# SI4689_Fm_Module.net
KiCad netlist of a schematic drawn in EAGLE
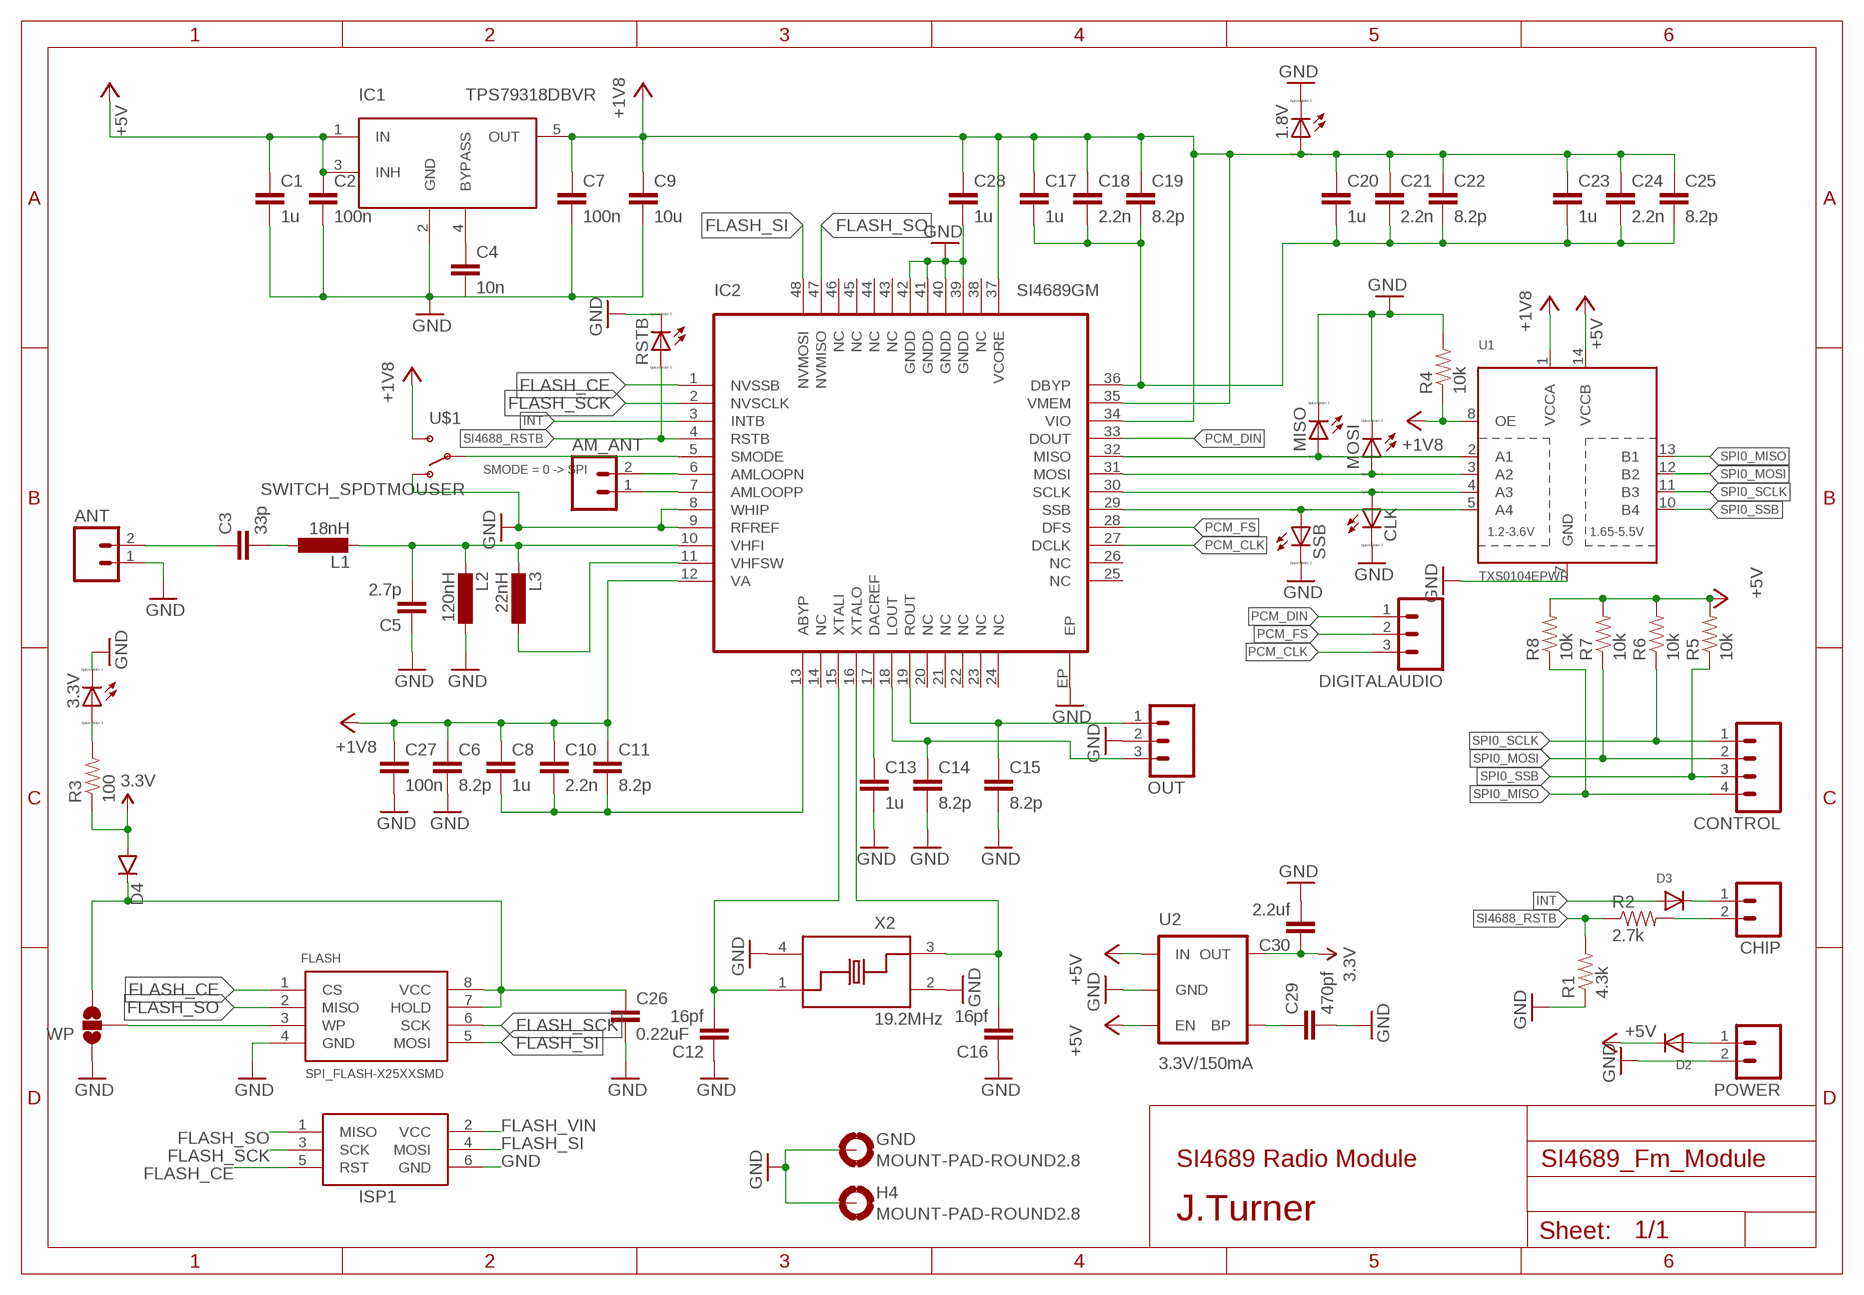
[diagram p0: schematic, sheet 1]

(export (version "E")
  (design (tool "Eeschema 10.0.6"))
  (components
    (comp (ref "1.8V")
      (value "LED_ESML0603")
      (footprint "eagle-import:LED_SML0603")
      (libsource (lib "eagle-import") (part "LED_ESML0603"))
    )
    (comp (ref "3.3V")
      (value "LED_ESML0603")
      (footprint "eagle-import:LED_SML0603")
      (libsource (lib "eagle-import") (part "LED_ESML0603"))
    )
    (comp (ref "AM_ANT")
      (value "M02")
      (footprint "eagle-import:02P")
      (libsource (lib "eagle-import") (part "M02"))
    )
    (comp (ref "ANT")
      (value "M02")
      (footprint "eagle-import:02P")
      (libsource (lib "eagle-import") (part "M02"))
    )
    (comp (ref "C1")
      (value "1u")
      (footprint "eagle-import:SMD0603")
      (libsource (lib "eagle-import") (part "C0603"))
    )
    (comp (ref "C2")
      (value "100n")
      (footprint "eagle-import:SMD0603")
      (libsource (lib "eagle-import") (part "C0603"))
    )
    (comp (ref "C3")
      (value "33p")
      (footprint "eagle-import:0603-CAP")
      (libsource (lib "eagle-import") (part "0603CAP"))
    )
    (comp (ref "C4")
      (value "10n")
      (footprint "eagle-import:SMD0603")
      (libsource (lib "eagle-import") (part "C0603"))
    )
    (comp (ref "C5")
      (value "2.7p")
      (footprint "eagle-import:0603-CAP")
      (libsource (lib "eagle-import") (part "0603CAP"))
    )
    (comp (ref "C6")
      (value "8.2p")
      (footprint "eagle-import:SMD0603")
      (libsource (lib "eagle-import") (part "C0603"))
    )
    (comp (ref "C7")
      (value "100n")
      (footprint "eagle-import:SMD0603")
      (libsource (lib "eagle-import") (part "C0603"))
    )
    (comp (ref "C8")
      (value "1u")
      (footprint "eagle-import:SMD0603")
      (libsource (lib "eagle-import") (part "C0603"))
    )
    (comp (ref "C9")
      (value "10u")
      (footprint "eagle-import:SMD0603")
      (libsource (lib "eagle-import") (part "C0603"))
    )
    (comp (ref "C10")
      (value "2.2n")
      (footprint "eagle-import:SMD0603")
      (libsource (lib "eagle-import") (part "C0603"))
    )
    (comp (ref "C11")
      (value "8.2p")
      (footprint "eagle-import:SMD0603")
      (libsource (lib "eagle-import") (part "C0603"))
    )
    (comp (ref "C12")
      (value "16pf")
      (footprint "eagle-import:0603-CAP")
      (libsource (lib "eagle-import") (part "0603CAP"))
    )
    (comp (ref "C13")
      (value "1u")
      (footprint "eagle-import:SMD0603")
      (libsource (lib "eagle-import") (part "C0603"))
    )
    (comp (ref "C14")
      (value "8.2p")
      (footprint "eagle-import:SMD0603")
      (libsource (lib "eagle-import") (part "C0603"))
    )
    (comp (ref "C15")
      (value "8.2p")
      (footprint "eagle-import:SMD0603")
      (libsource (lib "eagle-import") (part "C0603"))
    )
    (comp (ref "C16")
      (value "16pf")
      (footprint "eagle-import:0603-CAP")
      (libsource (lib "eagle-import") (part "0603CAP"))
    )
    (comp (ref "C17")
      (value "1u")
      (footprint "eagle-import:SMD0603")
      (libsource (lib "eagle-import") (part "C0603"))
    )
    (comp (ref "C18")
      (value "2.2n")
      (footprint "eagle-import:SMD0603")
      (libsource (lib "eagle-import") (part "C0603"))
    )
    (comp (ref "C19")
      (value "8.2p")
      (footprint "eagle-import:SMD0603")
      (libsource (lib "eagle-import") (part "C0603"))
    )
    (comp (ref "C20")
      (value "1u")
      (footprint "eagle-import:SMD0603")
      (libsource (lib "eagle-import") (part "C0603"))
    )
    (comp (ref "C21")
      (value "2.2n")
      (footprint "eagle-import:SMD0603")
      (libsource (lib "eagle-import") (part "C0603"))
    )
    (comp (ref "C22")
      (value "8.2p")
      (footprint "eagle-import:SMD0603")
      (libsource (lib "eagle-import") (part "C0603"))
    )
    (comp (ref "C23")
      (value "1u")
      (footprint "eagle-import:SMD0603")
      (libsource (lib "eagle-import") (part "C0603"))
    )
    (comp (ref "C24")
      (value "2.2n")
      (footprint "eagle-import:SMD0603")
      (libsource (lib "eagle-import") (part "C0603"))
    )
    (comp (ref "C25")
      (value "8.2p")
      (footprint "eagle-import:SMD0603")
      (libsource (lib "eagle-import") (part "C0603"))
    )
    (comp (ref "C26")
      (value "0.22uF")
      (footprint "eagle-import:0603-CAP")
      (libsource (lib "eagle-import") (part "0603CAP"))
    )
    (comp (ref "C27")
      (value "100n")
      (footprint "eagle-import:SMD0603")
      (libsource (lib "eagle-import") (part "C0603"))
    )
    (comp (ref "C28")
      (value "1u")
      (footprint "eagle-import:SMD0603")
      (libsource (lib "eagle-import") (part "C0603"))
    )
    (comp (ref "C29")
      (value "470pf")
      (footprint "eagle-import:0603-CAP")
      (libsource (lib "eagle-import") (part "0603CAP"))
    )
    (comp (ref "C30")
      (value "2.2uf")
      (footprint "eagle-import:0603-CAP")
      (libsource (lib "eagle-import") (part "0603CAP"))
    )
    (comp (ref "CHIP")
      (value "M02")
      (footprint "eagle-import:02P")
      (libsource (lib "eagle-import") (part "M02"))
    )
    (comp (ref "CLK")
      (value "LED_ESML0603")
      (footprint "eagle-import:LED_SML0603")
      (libsource (lib "eagle-import") (part "LED_ESML0603"))
    )
    (comp (ref "CONTROL")
      (value "M04")
      (footprint "eagle-import:04P")
      (libsource (lib "eagle-import") (part "M04"))
    )
    (comp (ref "D2")
      (value "DIODESOD-323F")
      (footprint "eagle-import:SOD-323F")
      (libsource (lib "eagle-import") (part "DIODESOD-323F"))
    )
    (comp (ref "D3")
      (value "DIODESOD-323F")
      (footprint "eagle-import:SOD-323F")
      (libsource (lib "eagle-import") (part "DIODESOD-323F"))
    )
    (comp (ref "D4")
      (value "DIODESOD523")
      (footprint "eagle-import:SOD523")
      (libsource (lib "eagle-import") (part "DIODESOD523"))
    )
    (comp (ref "DIGITALAUDIO")
      (value "M03")
      (footprint "eagle-import:03P")
      (libsource (lib "eagle-import") (part "M03"))
    )
    (comp (ref "FLASH")
      (value "SPI_FLASH-X25XXSMD")
      (footprint "eagle-import:SO08")
      (libsource (lib "eagle-import") (part "SPI_FLASH-X25XXSMD"))
    )
    (comp (ref "GND")
      (value "MOUNT-PAD-ROUND2.8")
      (footprint "eagle-import:2,8-PAD")
      (libsource (lib "eagle-import") (part "MOUNT-PAD-ROUND2.8"))
    )
    (comp (ref "H4")
      (value "MOUNT-PAD-ROUND2.8")
      (footprint "eagle-import:2,8-PAD")
      (libsource (lib "eagle-import") (part "MOUNT-PAD-ROUND2.8"))
    )
    (comp (ref "IC1")
      (value "TPS79318DBVR")
      (footprint "eagle-import:SOT23-5")
      (libsource (lib "eagle-import") (part "TPS79318DBVR"))
    )
    (comp (ref "IC2")
      (value "SI4689GM")
      (footprint "eagle-import:QFN48")
      (libsource (lib "eagle-import") (part "SI4689GM"))
    )
    (comp (ref "ISP1")
      (value "AVRISP-6")
      (footprint "eagle-import:AVRISP")
      (libsource (lib "eagle-import") (part "AVRISP-6"))
    )
    (comp (ref "L1")
      (value "18nH")
      (footprint "eagle-import:SMD0402")
      (libsource (lib "eagle-import") (part "L0402"))
    )
    (comp (ref "L2")
      (value "120nH")
      (footprint "eagle-import:SMD0402")
      (libsource (lib "eagle-import") (part "L0402"))
    )
    (comp (ref "L3")
      (value "22nH")
      (footprint "eagle-import:SMD0402")
      (libsource (lib "eagle-import") (part "L0402"))
    )
    (comp (ref "MISO")
      (value "LED_ESML0603")
      (footprint "eagle-import:LED_SML0603")
      (libsource (lib "eagle-import") (part "LED_ESML0603"))
    )
    (comp (ref "MOSI")
      (value "LED_ESML0603")
      (footprint "eagle-import:LED_SML0603")
      (libsource (lib "eagle-import") (part "LED_ESML0603"))
    )
    (comp (ref "OUT")
      (value "M03")
      (footprint "eagle-import:03P")
      (libsource (lib "eagle-import") (part "M03"))
    )
    (comp (ref "POWER")
      (value "M02")
      (footprint "eagle-import:02P")
      (libsource (lib "eagle-import") (part "M02"))
    )
    (comp (ref "R1")
      (value "4.3k")
      (footprint "eagle-import:0603-RES")
      (libsource (lib "eagle-import") (part "RESISTOR0603"))
    )
    (comp (ref "R2")
      (value "2.7k")
      (footprint "eagle-import:0603-RES")
      (libsource (lib "eagle-import") (part "RESISTOR0603"))
    )
    (comp (ref "R3")
      (value "100")
      (footprint "eagle-import:0603-RES")
      (libsource (lib "eagle-import") (part "RESISTOR0603"))
    )
    (comp (ref "R4")
      (value "10k")
      (footprint "eagle-import:0603-RES")
      (libsource (lib "eagle-import") (part "RESISTOR0603"))
    )
    (comp (ref "R5")
      (value "10k")
      (footprint "eagle-import:0603-RES")
      (libsource (lib "eagle-import") (part "RESISTOR0603"))
    )
    (comp (ref "R6")
      (value "10k")
      (footprint "eagle-import:0603-RES")
      (libsource (lib "eagle-import") (part "RESISTOR0603"))
    )
    (comp (ref "R7")
      (value "10k")
      (footprint "eagle-import:0603-RES")
      (libsource (lib "eagle-import") (part "RESISTOR0603"))
    )
    (comp (ref "R8")
      (value "10k")
      (footprint "eagle-import:0603-RES")
      (libsource (lib "eagle-import") (part "RESISTOR0603"))
    )
    (comp (ref "RSTB")
      (value "LED_ESML0603")
      (footprint "eagle-import:LED_SML0603")
      (libsource (lib "eagle-import") (part "LED_ESML0603"))
    )
    (comp (ref "SSB")
      (value "LED_ESML0603")
      (footprint "eagle-import:LED_SML0603")
      (libsource (lib "eagle-import") (part "LED_ESML0603"))
    )
    (comp (ref "U$1")
      (value "SWITCH_SPDTMOUSER")
      (footprint "eagle-import:SSSS810701")
      (libsource (lib "eagle-import") (part "SWITCH_SPDTMOUSER"))
    )
    (comp (ref "U1")
      (value "TXS0104EPWR")
      (footprint "eagle-import:TSSOP14")
      (libsource (lib "eagle-import") (part "TXS0104EPWR"))
    )
    (comp (ref "U2")
      (value "3.3V/150mA")
      (footprint "eagle-import:SOT23-5")
      (libsource (lib "eagle-import") (part "V_REG_MIC52053.3V"))
    )
    (comp (ref "WP")
      (value "SOLDERJUMPER_2WAYS")
      (footprint "eagle-import:SJ_3")
      (libsource (lib "eagle-import") (part "SOLDERJUMPER_2WAYS"))
    )
    (comp (ref "X2")
      (value "19.2MHz")
      (footprint "eagle-import:XTAL_3.2X2.5")
      (libsource (lib "eagle-import") (part "XTAL_3.2X2.5"))
    )
  )
  (nets
    (net (code "1") (name "+1V8") (class "Default")
      (node (ref "1.8V") (pin "A") (pinfunction "A_A") (pintype "passive"))
      (node (ref "C10") (pin "1") (pinfunction "1_1") (pintype "passive"))
      (node (ref "C11") (pin "1") (pinfunction "1_1") (pintype "passive"))
      (node (ref "C17") (pin "1") (pinfunction "1_1") (pintype "passive"))
      (node (ref "C18") (pin "1") (pinfunction "1_1") (pintype "passive"))
      (node (ref "C19") (pin "1") (pinfunction "1_1") (pintype "passive"))
      (node (ref "C20") (pin "1") (pinfunction "1_1") (pintype "passive"))
      (node (ref "C21") (pin "1") (pinfunction "1_1") (pintype "passive"))
      (node (ref "C22") (pin "1") (pinfunction "1_1") (pintype "passive"))
      (node (ref "C23") (pin "1") (pinfunction "1_1") (pintype "passive"))
      (node (ref "C24") (pin "1") (pinfunction "1_1") (pintype "passive"))
      (node (ref "C25") (pin "1") (pinfunction "1_1") (pintype "passive"))
      (node (ref "C27") (pin "1") (pinfunction "1_1") (pintype "passive"))
      (node (ref "C28") (pin "1") (pinfunction "1_1") (pintype "passive"))
      (node (ref "C6") (pin "1") (pinfunction "1_1") (pintype "passive"))
      (node (ref "C7") (pin "1") (pinfunction "1_1") (pintype "passive"))
      (node (ref "C8") (pin "1") (pinfunction "1_1") (pintype "passive"))
      (node (ref "C9") (pin "1") (pinfunction "1_1") (pintype "passive"))
      (node (ref "IC1") (pin "5") (pinfunction "OUT_5") (pintype "power_in"))
      (node (ref "IC2") (pin "12") (pinfunction "VA_12") (pintype "power_in"))
      (node (ref "IC2") (pin "34") (pinfunction "VIO_34") (pintype "power_in"))
      (node (ref "IC2") (pin "35") (pinfunction "VMEM_35") (pintype "power_in"))
      (node (ref "IC2") (pin "37") (pinfunction "VCORE_37") (pintype "power_in"))
      (node (ref "R4") (pin "1") (pinfunction "1_1") (pintype "passive"))
      (node (ref "U$1") (pin "S") (pinfunction "S_S") (pintype "passive"))
      (node (ref "U1") (pin "1") (pinfunction "VCCA_1") (pintype "bidirectional"))
      (node (ref "U1") (pin "8") (pinfunction "OE_8") (pintype "bidirectional"))
    )
    (net (code "2") (name "+5V") (class "Default")
      (node (ref "C1") (pin "1") (pinfunction "1_1") (pintype "passive"))
      (node (ref "C2") (pin "1") (pinfunction "1_1") (pintype "passive"))
      (node (ref "D2") (pin "C") (pinfunction "C_C") (pintype "passive"))
      (node (ref "IC1") (pin "1") (pinfunction "IN_1") (pintype "power_in"))
      (node (ref "IC1") (pin "3") (pinfunction "INH_3") (pintype "input"))
      (node (ref "R5") (pin "2") (pinfunction "2_2") (pintype "passive"))
      (node (ref "R6") (pin "2") (pinfunction "2_2") (pintype "passive"))
      (node (ref "R7") (pin "2") (pinfunction "2_2") (pintype "passive"))
      (node (ref "R8") (pin "2") (pinfunction "2_2") (pintype "passive"))
      (node (ref "U1") (pin "14") (pinfunction "VCCB_14") (pintype "bidirectional"))
      (node (ref "U2") (pin "1") (pinfunction "IN_1") (pintype "input"))
      (node (ref "U2") (pin "3") (pinfunction "EN_3") (pintype "input"))
    )
    (net (code "3") (name "/FLASH_VIN") (class "Default")
      (node (ref "C26") (pin "1") (pinfunction "1_1") (pintype "passive"))
      (node (ref "D4") (pin "C") (pinfunction "C_C") (pintype "passive"))
      (node (ref "FLASH") (pin "7") (pinfunction "HOLD_7") (pintype "bidirectional"))
      (node (ref "FLASH") (pin "8") (pinfunction "VCC_8") (pintype "bidirectional"))
      (node (ref "ISP1") (pin "2") (pinfunction "VCC_2") (pintype "power_in"))
      (node (ref "WP") (pin "3") (pinfunction "3_3") (pintype "passive"))
    )
    (net (code "4") (name "3.3V") (class "Default")
      (node (ref "C30") (pin "1") (pinfunction "1_1") (pintype "passive"))
      (node (ref "D4") (pin "A") (pinfunction "A_A") (pintype "passive"))
      (node (ref "R3") (pin "1") (pinfunction "1_1") (pintype "passive"))
      (node (ref "U2") (pin "5") (pinfunction "OUT_5") (pintype "passive"))
    )
    (net (code "5") (name "FLASH_CE") (class "Default")
      (node (ref "FLASH") (pin "1") (pinfunction "CS_1") (pintype "bidirectional"))
      (node (ref "IC2") (pin "1") (pinfunction "NVSSB_1") (pintype "output"))
      (node (ref "ISP1") (pin "5") (pinfunction "RST_5") (pintype "output"))
    )
    (net (code "6") (name "FLASH_SCK") (class "Default")
      (node (ref "FLASH") (pin "6") (pinfunction "SCK_6") (pintype "bidirectional"))
      (node (ref "IC2") (pin "2") (pinfunction "NVSCLK_2") (pintype "output"))
      (node (ref "ISP1") (pin "3") (pinfunction "SCK_3") (pintype "output"))
    )
    (net (code "7") (name "FLASH_SI") (class "Default")
      (node (ref "FLASH") (pin "5") (pinfunction "MOSI_5") (pintype "bidirectional"))
      (node (ref "IC2") (pin "48") (pinfunction "NVMOSI_48") (pintype "output"))
      (node (ref "ISP1") (pin "4") (pinfunction "MOSI_4") (pintype "output"))
    )
    (net (code "8") (name "FLASH_SO") (class "Default")
      (node (ref "FLASH") (pin "2") (pinfunction "MISO_2") (pintype "bidirectional"))
      (node (ref "IC2") (pin "47") (pinfunction "NVMISO_47") (pintype "input"))
      (node (ref "ISP1") (pin "1") (pinfunction "MISO_1") (pintype "input"))
    )
    (net (code "9") (name "GND") (class "Default")
      (node (ref "1.8V") (pin "C") (pinfunction "C_C") (pintype "passive"))
      (node (ref "3.3V") (pin "C") (pinfunction "C_C") (pintype "passive"))
      (node (ref "ANT") (pin "1") (pinfunction "1_1") (pintype "passive"))
      (node (ref "C1") (pin "2") (pinfunction "2_2") (pintype "passive"))
      (node (ref "C12") (pin "1") (pinfunction "1_1") (pintype "passive"))
      (node (ref "C13") (pin "2") (pinfunction "2_2") (pintype "passive"))
      (node (ref "C14") (pin "2") (pinfunction "2_2") (pintype "passive"))
      (node (ref "C15") (pin "2") (pinfunction "2_2") (pintype "passive"))
      (node (ref "C16") (pin "1") (pinfunction "1_1") (pintype "passive"))
      (node (ref "C2") (pin "2") (pinfunction "2_2") (pintype "passive"))
      (node (ref "C26") (pin "2") (pinfunction "2_2") (pintype "passive"))
      (node (ref "C27") (pin "2") (pinfunction "2_2") (pintype "passive"))
      (node (ref "C28") (pin "2") (pinfunction "2_2") (pintype "passive"))
      (node (ref "C29") (pin "2") (pinfunction "2_2") (pintype "passive"))
      (node (ref "C30") (pin "2") (pinfunction "2_2") (pintype "passive"))
      (node (ref "C4") (pin "2") (pinfunction "2_2") (pintype "passive"))
      (node (ref "C5") (pin "1") (pinfunction "1_1") (pintype "passive"))
      (node (ref "C6") (pin "2") (pinfunction "2_2") (pintype "passive"))
      (node (ref "C7") (pin "2") (pinfunction "2_2") (pintype "passive"))
      (node (ref "C9") (pin "2") (pinfunction "2_2") (pintype "passive"))
      (node (ref "CLK") (pin "C") (pinfunction "C_C") (pintype "passive"))
      (node (ref "FLASH") (pin "4") (pinfunction "GND_4") (pintype "bidirectional"))
      (node (ref "GND") (pin "B2,8") (pinfunction "MOUNT_B2,8") (pintype "passive"))
      (node (ref "H4") (pin "B2,8") (pinfunction "MOUNT_B2,8") (pintype "passive"))
      (node (ref "IC1") (pin "2") (pinfunction "GND_2") (pintype "power_in"))
      (node (ref "IC2") (pin "39") (pinfunction "GNDD_39") (pintype "power_in"))
      (node (ref "IC2") (pin "40") (pinfunction "GNDD_40") (pintype "power_in"))
      (node (ref "IC2") (pin "41") (pinfunction "GNDD_41") (pintype "power_in"))
      (node (ref "IC2") (pin "42") (pinfunction "GNDD_42") (pintype "power_in"))
      (node (ref "IC2") (pin "8") (pinfunction "WHIP_8") (pintype "power_in"))
      (node (ref "IC2") (pin "9") (pinfunction "RFREF_9") (pintype "power_in"))
      (node (ref "IC2") (pin "EP") (pinfunction "EP_EP") (pintype "bidirectional"))
      (node (ref "ISP1") (pin "6") (pinfunction "GND_6") (pintype "power_in"))
      (node (ref "L2") (pin "1") (pinfunction "1_1") (pintype "passive"))
      (node (ref "MISO") (pin "C") (pinfunction "C_C") (pintype "passive"))
      (node (ref "MOSI") (pin "C") (pinfunction "C_C") (pintype "passive"))
      (node (ref "OUT") (pin "2") (pinfunction "2_2") (pintype "passive"))
      (node (ref "POWER") (pin "2") (pinfunction "2_2") (pintype "passive"))
      (node (ref "R1") (pin "1") (pinfunction "1_1") (pintype "passive"))
      (node (ref "R4") (pin "2") (pinfunction "2_2") (pintype "passive"))
      (node (ref "RSTB") (pin "C") (pinfunction "C_C") (pintype "passive"))
      (node (ref "SSB") (pin "C") (pinfunction "C_C") (pintype "passive"))
      (node (ref "U$1") (pin "O") (pinfunction "O_O") (pintype "passive"))
      (node (ref "U1") (pin "7") (pinfunction "GND_7") (pintype "bidirectional"))
      (node (ref "U2") (pin "2") (pinfunction "GND_2") (pintype "input"))
      (node (ref "WP") (pin "1") (pinfunction "1_1") (pintype "passive"))
      (node (ref "X2") (pin "2") (pinfunction "GND_2") (pintype "power_in"))
      (node (ref "X2") (pin "4") (pinfunction "GND_4") (pintype "power_in"))
    )
    (net (code "10") (name "INT") (class "Default")
      (node (ref "D3") (pin "A") (pinfunction "A_A") (pintype "passive"))
      (node (ref "IC2") (pin "3") (pinfunction "INTB_3") (pintype "output"))
    )
    (net (code "11") (name "Net-(3.3V-PadA)") (class "Default")
      (node (ref "3.3V") (pin "A") (pinfunction "A_A") (pintype "passive"))
      (node (ref "R3") (pin "2") (pinfunction "2_2") (pintype "passive"))
    )
    (net (code "12") (name "Net-(ANT-Pad2)") (class "Default")
      (node (ref "ANT") (pin "2") (pinfunction "2_2") (pintype "passive"))
      (node (ref "C3") (pin "1") (pinfunction "1_1") (pintype "passive"))
    )
    (net (code "13") (name "Net-(C3-Pad2)") (class "Default")
      (node (ref "C3") (pin "2") (pinfunction "2_2") (pintype "passive"))
      (node (ref "L1") (pin "1") (pinfunction "1_1") (pintype "passive"))
    )
    (net (code "14") (name "Net-(CHIP-Pad1)") (class "Default")
      (node (ref "CHIP") (pin "1") (pinfunction "1_1") (pintype "passive"))
      (node (ref "D3") (pin "C") (pinfunction "C_C") (pintype "passive"))
    )
    (net (code "15") (name "Net-(CHIP-Pad2)") (class "Default")
      (node (ref "CHIP") (pin "2") (pinfunction "2_2") (pintype "passive"))
      (node (ref "R2") (pin "2") (pinfunction "2_2") (pintype "passive"))
    )
    (net (code "16") (name "Net-(D2-PadA)") (class "Default")
      (node (ref "D2") (pin "A") (pinfunction "A_A") (pintype "passive"))
      (node (ref "POWER") (pin "1") (pinfunction "1_1") (pintype "passive"))
    )
    (net (code "17") (name "Net-(FLASH-WP)") (class "Default")
      (node (ref "FLASH") (pin "3") (pinfunction "WP_3") (pintype "bidirectional"))
      (node (ref "WP") (pin "2") (pinfunction "2_2") (pintype "passive"))
    )
    (net (code "18") (name "Net-(IC1-BYPASS)") (class "Default")
      (node (ref "C4") (pin "1") (pinfunction "1_1") (pintype "passive"))
      (node (ref "IC1") (pin "4") (pinfunction "BYPASS_4") (pintype "power_in"))
    )
    (net (code "19") (name "Net-(IC2-ABYP)") (class "Default")
      (node (ref "C10") (pin "2") (pinfunction "2_2") (pintype "passive"))
      (node (ref "C11") (pin "2") (pinfunction "2_2") (pintype "passive"))
      (node (ref "C8") (pin "2") (pinfunction "2_2") (pintype "passive"))
      (node (ref "IC2") (pin "13") (pinfunction "ABYP_13") (pintype "power_in"))
    )
    (net (code "20") (name "Net-(IC2-AMLOOPN)") (class "Default")
      (node (ref "AM_ANT") (pin "2") (pinfunction "2_2") (pintype "passive"))
      (node (ref "IC2") (pin "6") (pinfunction "AMLOOPN_6") (pintype "power_in"))
    )
    (net (code "21") (name "Net-(IC2-AMLOOPP)") (class "Default")
      (node (ref "AM_ANT") (pin "1") (pinfunction "1_1") (pintype "passive"))
      (node (ref "IC2") (pin "7") (pinfunction "AMLOOPP_7") (pintype "power_in"))
    )
    (net (code "22") (name "Net-(IC2-DACREF)") (class "Default")
      (node (ref "C13") (pin "1") (pinfunction "1_1") (pintype "passive"))
      (node (ref "IC2") (pin "17") (pinfunction "DACREF_17") (pintype "power_in"))
    )
    (net (code "23") (name "Net-(IC2-DBYP)") (class "Default")
      (node (ref "C17") (pin "2") (pinfunction "2_2") (pintype "passive"))
      (node (ref "C18") (pin "2") (pinfunction "2_2") (pintype "passive"))
      (node (ref "C19") (pin "2") (pinfunction "2_2") (pintype "passive"))
      (node (ref "C20") (pin "2") (pinfunction "2_2") (pintype "passive"))
      (node (ref "C21") (pin "2") (pinfunction "2_2") (pintype "passive"))
      (node (ref "C22") (pin "2") (pinfunction "2_2") (pintype "passive"))
      (node (ref "C23") (pin "2") (pinfunction "2_2") (pintype "passive"))
      (node (ref "C24") (pin "2") (pinfunction "2_2") (pintype "passive"))
      (node (ref "C25") (pin "2") (pinfunction "2_2") (pintype "passive"))
      (node (ref "IC2") (pin "36") (pinfunction "DBYP_36") (pintype "power_in"))
    )
    (net (code "24") (name "Net-(IC2-LOUT)") (class "Default")
      (node (ref "C14") (pin "1") (pinfunction "1_1") (pintype "passive"))
      (node (ref "IC2") (pin "18") (pinfunction "LOUT_18") (pintype "output"))
      (node (ref "OUT") (pin "3") (pinfunction "3_3") (pintype "passive"))
    )
    (net (code "25") (name "Net-(IC2-MISO)") (class "Default")
      (node (ref "IC2") (pin "32") (pinfunction "MISO_32") (pintype "bidirectional"))
      (node (ref "MISO") (pin "A") (pinfunction "A_A") (pintype "passive"))
      (node (ref "U1") (pin "2") (pinfunction "A1_2") (pintype "bidirectional"))
    )
    (net (code "26") (name "Net-(IC2-MOSI)") (class "Default")
      (node (ref "IC2") (pin "31") (pinfunction "MOSI_31") (pintype "bidirectional"))
      (node (ref "MOSI") (pin "A") (pinfunction "A_A") (pintype "passive"))
      (node (ref "U1") (pin "3") (pinfunction "A2_3") (pintype "bidirectional"))
    )
    (net (code "27") (name "Net-(IC2-ROUT)") (class "Default")
      (node (ref "C15") (pin "1") (pinfunction "1_1") (pintype "passive"))
      (node (ref "IC2") (pin "19") (pinfunction "ROUT_19") (pintype "output"))
      (node (ref "OUT") (pin "1") (pinfunction "1_1") (pintype "passive"))
    )
    (net (code "28") (name "Net-(IC2-SCLK)") (class "Default")
      (node (ref "CLK") (pin "A") (pinfunction "A_A") (pintype "passive"))
      (node (ref "IC2") (pin "30") (pinfunction "SCLK_30") (pintype "input"))
      (node (ref "U1") (pin "4") (pinfunction "A3_4") (pintype "bidirectional"))
    )
    (net (code "29") (name "Net-(IC2-SMODE)") (class "Default")
      (node (ref "IC2") (pin "5") (pinfunction "SMODE_5") (pintype "input"))
      (node (ref "U$1") (pin "P") (pinfunction "P_P") (pintype "passive"))
    )
    (net (code "30") (name "Net-(IC2-SSB)") (class "Default")
      (node (ref "IC2") (pin "29") (pinfunction "SSB_29") (pintype "input"))
      (node (ref "SSB") (pin "A") (pinfunction "A_A") (pintype "passive"))
      (node (ref "U1") (pin "5") (pinfunction "A4_5") (pintype "bidirectional"))
    )
    (net (code "31") (name "Net-(IC2-VHFI)") (class "Default")
      (node (ref "C5") (pin "2") (pinfunction "2_2") (pintype "passive"))
      (node (ref "IC2") (pin "10") (pinfunction "VHFI_10") (pintype "input"))
      (node (ref "L1") (pin "2") (pinfunction "2_2") (pintype "passive"))
      (node (ref "L2") (pin "2") (pinfunction "2_2") (pintype "passive"))
      (node (ref "L3") (pin "2") (pinfunction "2_2") (pintype "passive"))
    )
    (net (code "32") (name "Net-(IC2-VHFSW)") (class "Default")
      (node (ref "IC2") (pin "11") (pinfunction "VHFSW_11") (pintype "output"))
      (node (ref "L3") (pin "1") (pinfunction "1_1") (pintype "passive"))
    )
    (net (code "33") (name "Net-(IC2-XTALI)") (class "Default")
      (node (ref "C12") (pin "2") (pinfunction "2_2") (pintype "passive"))
      (node (ref "IC2") (pin "15") (pinfunction "XTALI_15") (pintype "input"))
      (node (ref "X2") (pin "1") (pinfunction "1_1") (pintype "passive"))
    )
    (net (code "34") (name "Net-(IC2-XTALO)") (class "Default")
      (node (ref "C16") (pin "2") (pinfunction "2_2") (pintype "passive"))
      (node (ref "IC2") (pin "16") (pinfunction "XTALO_16") (pintype "output"))
      (node (ref "X2") (pin "3") (pinfunction "3_3") (pintype "passive"))
    )
    (net (code "35") (name "Net-(U2-BP)") (class "Default")
      (node (ref "C29") (pin "1") (pinfunction "1_1") (pintype "passive"))
      (node (ref "U2") (pin "4") (pinfunction "BP_4") (pintype "input"))
    )
    (net (code "36") (name "PCM_CLK") (class "Default")
      (node (ref "DIGITALAUDIO") (pin "3") (pinfunction "3_3") (pintype "passive"))
      (node (ref "IC2") (pin "27") (pinfunction "DCLK_27") (pintype "bidirectional"))
    )
    (net (code "37") (name "PCM_DIN") (class "Default")
      (node (ref "DIGITALAUDIO") (pin "1") (pinfunction "1_1") (pintype "passive"))
      (node (ref "IC2") (pin "33") (pinfunction "DOUT_33") (pintype "output"))
    )
    (net (code "38") (name "PCM_FS") (class "Default")
      (node (ref "DIGITALAUDIO") (pin "2") (pinfunction "2_2") (pintype "passive"))
      (node (ref "IC2") (pin "28") (pinfunction "DFS_28") (pintype "bidirectional"))
    )
    (net (code "39") (name "SI4688_RSTB") (class "Default")
      (node (ref "IC2") (pin "4") (pinfunction "RSTB_4") (pintype "input"))
      (node (ref "R1") (pin "2") (pinfunction "2_2") (pintype "passive"))
      (node (ref "R2") (pin "1") (pinfunction "1_1") (pintype "passive"))
      (node (ref "RSTB") (pin "A") (pinfunction "A_A") (pintype "passive"))
    )
    (net (code "40") (name "SPI0_MISO") (class "Default")
      (node (ref "CONTROL") (pin "4") (pinfunction "4_4") (pintype "passive"))
      (node (ref "R8") (pin "1") (pinfunction "1_1") (pintype "passive"))
      (node (ref "U1") (pin "13") (pinfunction "B1_13") (pintype "bidirectional"))
    )
    (net (code "41") (name "SPI0_MOSI") (class "Default")
      (node (ref "CONTROL") (pin "2") (pinfunction "2_2") (pintype "passive"))
      (node (ref "R7") (pin "1") (pinfunction "1_1") (pintype "passive"))
      (node (ref "U1") (pin "12") (pinfunction "B2_12") (pintype "bidirectional"))
    )
    (net (code "42") (name "SPI0_SCLK") (class "Default")
      (node (ref "CONTROL") (pin "1") (pinfunction "1_1") (pintype "passive"))
      (node (ref "R6") (pin "1") (pinfunction "1_1") (pintype "passive"))
      (node (ref "U1") (pin "11") (pinfunction "B3_11") (pintype "bidirectional"))
    )
    (net (code "43") (name "SPI0_SSB") (class "Default")
      (node (ref "CONTROL") (pin "3") (pinfunction "3_3") (pintype "passive"))
      (node (ref "R5") (pin "1") (pinfunction "1_1") (pintype "passive"))
      (node (ref "U1") (pin "10") (pinfunction "B4_10") (pintype "bidirectional"))
    )
    (net (code "44") (name "unconnected-(IC2-NC-Pad14)") (class "Default")
      (node (ref "IC2") (pin "14") (pinfunction "NC_14") (pintype "no_connect"))
    )
    (net (code "45") (name "unconnected-(IC2-NC-Pad20)") (class "Default")
      (node (ref "IC2") (pin "20") (pinfunction "NC_20") (pintype "no_connect"))
    )
    (net (code "46") (name "unconnected-(IC2-NC-Pad21)") (class "Default")
      (node (ref "IC2") (pin "21") (pinfunction "NC_21") (pintype "no_connect"))
    )
    (net (code "47") (name "unconnected-(IC2-NC-Pad22)") (class "Default")
      (node (ref "IC2") (pin "22") (pinfunction "NC_22") (pintype "no_connect"))
    )
    (net (code "48") (name "unconnected-(IC2-NC-Pad23)") (class "Default")
      (node (ref "IC2") (pin "23") (pinfunction "NC_23") (pintype "no_connect"))
    )
    (net (code "49") (name "unconnected-(IC2-NC-Pad24)") (class "Default")
      (node (ref "IC2") (pin "24") (pinfunction "NC_24") (pintype "no_connect"))
    )
    (net (code "50") (name "unconnected-(IC2-NC-Pad25)") (class "Default")
      (node (ref "IC2") (pin "25") (pinfunction "NC_25") (pintype "no_connect"))
    )
    (net (code "51") (name "unconnected-(IC2-NC-Pad26)") (class "Default")
      (node (ref "IC2") (pin "26") (pinfunction "NC_26") (pintype "no_connect"))
    )
    (net (code "52") (name "unconnected-(IC2-NC-Pad38)") (class "Default")
      (node (ref "IC2") (pin "38") (pinfunction "NC_38") (pintype "no_connect"))
    )
    (net (code "53") (name "unconnected-(IC2-NC-Pad43)") (class "Default")
      (node (ref "IC2") (pin "43") (pinfunction "NC_43") (pintype "no_connect"))
    )
    (net (code "54") (name "unconnected-(IC2-NC-Pad44)") (class "Default")
      (node (ref "IC2") (pin "44") (pinfunction "NC_44") (pintype "no_connect"))
    )
    (net (code "55") (name "unconnected-(IC2-NC-Pad45)") (class "Default")
      (node (ref "IC2") (pin "45") (pinfunction "NC_45") (pintype "no_connect"))
    )
    (net (code "56") (name "unconnected-(IC2-NC-Pad46)") (class "Default")
      (node (ref "IC2") (pin "46") (pinfunction "NC_46") (pintype "no_connect"))
    )
  )
)
